# Sheet_1_2022-01-26.net
KiCad netlist of a schematic drawn in Altium Designer
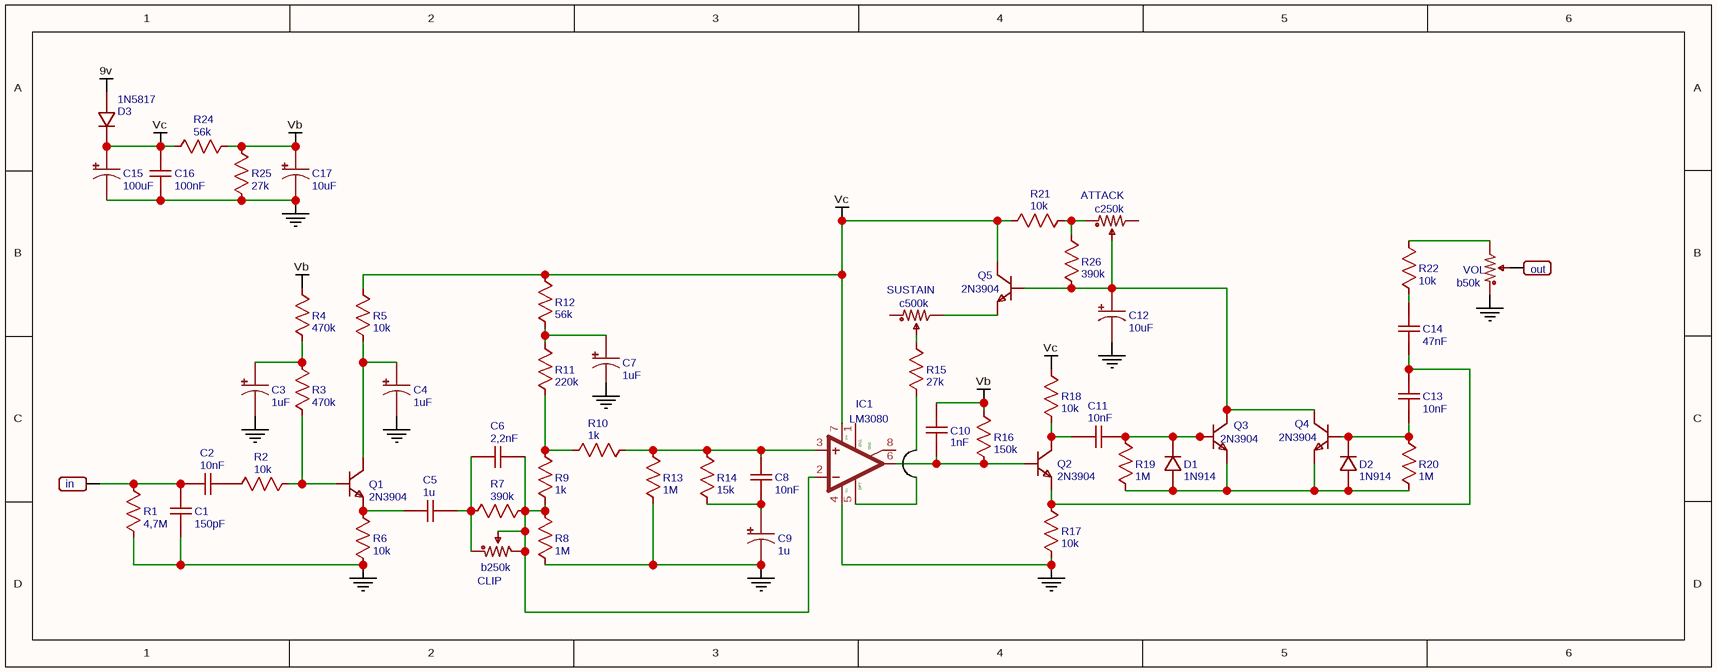
[diagram p0: Sheet_1_2022-01-26.schdoc]

(export (version "E")
  (design (tool "Eeschema 10.0.6"))
  (components
    (comp (ref "ATTACK")
      (value "c250k")
      (fields
        (field (name "BOM_SUPPLIER PART") "C125022")
        (field (name "BOM_MANUFACTURER PART") "3386P-1-101LF")
        (field (name "CONTRIBUTOR") "EasyEDA")
      )
      (libsource (lib "altium-import") (part "root_0_c250k_"))
    )
    (comp (ref "C1")
      (value "150pF")
      (fields (field (name "BOM_MANUFACTURER PART") "?"))
      (libsource (lib "altium-import") (part "root_0_150pF_"))
    )
    (comp (ref "C2")
      (value "10nF")
      (fields (field (name "BOM_MANUFACTURER PART") "?"))
      (libsource (lib "altium-import") (part "root_1_10nF_"))
    )
    (comp (ref "C3")
      (value "1uF")
      (fields (field (name "BOM_MANUFACTURER PART") "?"))
      (libsource (lib "altium-import") (part "root_0_1uF_"))
    )
    (comp (ref "C4")
      (value "1uF")
      (fields (field (name "BOM_MANUFACTURER PART") "?"))
      (libsource (lib "altium-import") (part "root_0_1uF_"))
    )
    (comp (ref "C5")
      (value "1u")
      (fields (field (name "BOM_MANUFACTURER PART") "?"))
      (libsource (lib "altium-import") (part "root_1_1u_"))
    )
    (comp (ref "C6")
      (value "2,2nF")
      (fields (field (name "BOM_MANUFACTURER PART") "?"))
      (libsource (lib "altium-import") (part "root_1_2,2nF_"))
    )
    (comp (ref "C7")
      (value "1uF")
      (fields (field (name "BOM_MANUFACTURER PART") "?"))
      (libsource (lib "altium-import") (part "root_0_1uF_"))
    )
    (comp (ref "C8")
      (value "10nF")
      (fields (field (name "BOM_MANUFACTURER PART") "?"))
      (libsource (lib "altium-import") (part "root_0_10nF_"))
    )
    (comp (ref "C9")
      (value "1u")
      (fields (field (name "BOM_MANUFACTURER PART") "?"))
      (libsource (lib "altium-import") (part "root_0_1u_"))
    )
    (comp (ref "C10")
      (value "1nF")
      (fields (field (name "BOM_MANUFACTURER PART") "?"))
      (libsource (lib "altium-import") (part "root_0_1nF_"))
    )
    (comp (ref "C11")
      (value "10nF")
      (fields (field (name "BOM_MANUFACTURER PART") "?"))
      (libsource (lib "altium-import") (part "root_1_10nF_"))
    )
    (comp (ref "C12")
      (value "10uF")
      (fields (field (name "BOM_MANUFACTURER PART") "?"))
      (libsource (lib "altium-import") (part "root_0_10uF_"))
    )
    (comp (ref "C13")
      (value "10nF")
      (fields (field (name "BOM_MANUFACTURER PART") "?"))
      (libsource (lib "altium-import") (part "root_0_10nF_"))
    )
    (comp (ref "C14")
      (value "47nF")
      (fields (field (name "BOM_MANUFACTURER PART") "?"))
      (libsource (lib "altium-import") (part "root_0_47nF_"))
    )
    (comp (ref "C15")
      (value "100uF")
      (fields (field (name "BOM_MANUFACTURER PART") "?"))
      (libsource (lib "altium-import") (part "root_0_100uF_"))
    )
    (comp (ref "C16")
      (value "100nF")
      (fields (field (name "BOM_MANUFACTURER PART") "?"))
      (libsource (lib "altium-import") (part "root_0_100nF_"))
    )
    (comp (ref "C17")
      (value "10uF")
      (fields (field (name "BOM_MANUFACTURER PART") "?"))
      (libsource (lib "altium-import") (part "root_0_10uF_"))
    )
    (comp (ref "CLIP")
      (value "b250k")
      (fields
        (field (name "BOM_SUPPLIER PART") "C125022")
        (field (name "BOM_MANUFACTURER PART") "3386P-1-101LF")
        (field (name "CONTRIBUTOR") "EasyEDA")
      )
      (libsource (lib "altium-import") (part "root_0_b250k_"))
    )
    (comp (ref "D1")
      (value "1N914")
      (fields (field (name "BOM_SUPPLIER PART") "C54037") (field (name "BOM_MANUFACTURER PART") "1N4448"))
      (libsource (lib "altium-import") (part "root_1_1N914_"))
    )
    (comp (ref "D2")
      (value "1N914")
      (fields (field (name "BOM_SUPPLIER PART") "C54037") (field (name "BOM_MANUFACTURER PART") "1N4448"))
      (libsource (lib "altium-import") (part "root_1_1N914_"))
    )
    (comp (ref "D3")
      (value "1N5817")
      (fields (field (name "BOM_SUPPLIER PART") "C54037") (field (name "BOM_MANUFACTURER PART") "1N4448"))
      (libsource (lib "altium-import") (part "root_1_1N5817_"))
    )
    (comp (ref "IC1")
      (value "LM3080")
      (description "OP AMP")
      (fields (field (name "BOM_MANUFACTURER PART") "?"))
      (libsource (lib "altium-import") (part "root_0_LM3080_"))
    )
    (comp (ref "P1")
      (value "in")
      (fields
        (field (name "BOM_SUPPLIER PART") "C81276")
        (field (name "BOM_MANUFACTURER PART") "Header-Male-2.54_1x1")
      )
      (libsource (lib "altium-import") (part "root_0_in_"))
    )
    (comp (ref "P2")
      (value "out")
      (fields
        (field (name "BOM_SUPPLIER PART") "C81276")
        (field (name "BOM_MANUFACTURER PART") "Header-Male-2.54_1x1")
      )
      (libsource (lib "altium-import") (part "root_0_out_"))
    )
    (comp (ref "Q1")
      (value "2N3904")
      (fields (field (name "BOM_SUPPLIER PART") "C118538"))
      (libsource (lib "") (part "root_0_2N3904__1"))
    )
    (comp (ref "Q2")
      (value "2N3904")
      (fields (field (name "BOM_SUPPLIER PART") "C118538"))
      (libsource (lib "") (part "root_0_2N3904__1"))
    )
    (comp (ref "Q3")
      (value "2N3904")
      (fields (field (name "BOM_SUPPLIER PART") "C118538"))
      (libsource (lib "") (part "root_0_2N3904__1"))
    )
    (comp (ref "Q4")
      (value "2N3904")
      (fields (field (name "BOM_SUPPLIER PART") "C118538"))
      (libsource (lib "altium-import") (part "root_0_2N3904_"))
    )
    (comp (ref "Q5")
      (value "2N3904")
      (fields (field (name "BOM_SUPPLIER PART") "C118538"))
      (libsource (lib "altium-import") (part "root_0_2N3904_"))
    )
    (comp (ref "R1")
      (value "4,7M")
      (fields (field (name "BOM_MANUFACTURER PART") "?"))
      (libsource (lib "altium-import") (part "root_1_4,7M_"))
    )
    (comp (ref "R2")
      (value "10k")
      (fields (field (name "BOM_MANUFACTURER PART") "?"))
      (libsource (lib "altium-import") (part "root_0_10k_"))
    )
    (comp (ref "R3")
      (value "470k")
      (fields (field (name "BOM_MANUFACTURER PART") "?"))
      (libsource (lib "altium-import") (part "root_1_470k_"))
    )
    (comp (ref "R4")
      (value "470k")
      (fields (field (name "BOM_MANUFACTURER PART") "?"))
      (libsource (lib "altium-import") (part "root_1_470k_"))
    )
    (comp (ref "R5")
      (value "10k")
      (fields (field (name "BOM_MANUFACTURER PART") "?"))
      (libsource (lib "altium-import") (part "root_1_10k_"))
    )
    (comp (ref "R6")
      (value "10k")
      (fields (field (name "BOM_MANUFACTURER PART") "?"))
      (libsource (lib "altium-import") (part "root_1_10k_"))
    )
    (comp (ref "R7")
      (value "390k")
      (fields (field (name "BOM_MANUFACTURER PART") "?"))
      (libsource (lib "altium-import") (part "root_0_390k_"))
    )
    (comp (ref "R8")
      (value "1M")
      (fields (field (name "BOM_MANUFACTURER PART") "?"))
      (libsource (lib "altium-import") (part "root_1_1M_"))
    )
    (comp (ref "R9")
      (value "1k")
      (fields (field (name "BOM_MANUFACTURER PART") "?"))
      (libsource (lib "altium-import") (part "root_1_1k_"))
    )
    (comp (ref "R10")
      (value "1k")
      (fields (field (name "BOM_MANUFACTURER PART") "?"))
      (libsource (lib "altium-import") (part "root_2_1k_"))
    )
    (comp (ref "R11")
      (value "220k")
      (fields (field (name "BOM_MANUFACTURER PART") "?"))
      (libsource (lib "altium-import") (part "root_1_220k_"))
    )
    (comp (ref "R12")
      (value "56k")
      (fields (field (name "BOM_MANUFACTURER PART") "?"))
      (libsource (lib "altium-import") (part "root_1_56k_"))
    )
    (comp (ref "R13")
      (value "1M")
      (fields (field (name "BOM_MANUFACTURER PART") "?"))
      (libsource (lib "altium-import") (part "root_1_1M_"))
    )
    (comp (ref "R14")
      (value "15k")
      (fields (field (name "BOM_MANUFACTURER PART") "?"))
      (libsource (lib "altium-import") (part "root_1_15k_"))
    )
    (comp (ref "R15")
      (value "27k")
      (fields (field (name "BOM_MANUFACTURER PART") "?"))
      (libsource (lib "altium-import") (part "root_1_27k_"))
    )
    (comp (ref "R16")
      (value "150k")
      (fields (field (name "BOM_MANUFACTURER PART") "?"))
      (libsource (lib "altium-import") (part "root_1_150k_"))
    )
    (comp (ref "R17")
      (value "10k")
      (fields (field (name "BOM_MANUFACTURER PART") "?"))
      (libsource (lib "altium-import") (part "root_1_10k_"))
    )
    (comp (ref "R18")
      (value "10k")
      (fields (field (name "BOM_MANUFACTURER PART") "?"))
      (libsource (lib "altium-import") (part "root_1_10k_"))
    )
    (comp (ref "R19")
      (value "1M")
      (fields (field (name "BOM_MANUFACTURER PART") "?"))
      (libsource (lib "altium-import") (part "root_1_1M_"))
    )
    (comp (ref "R20")
      (value "1M")
      (fields (field (name "BOM_MANUFACTURER PART") "?"))
      (libsource (lib "altium-import") (part "root_1_1M_"))
    )
    (comp (ref "R21")
      (value "10k")
      (fields (field (name "BOM_MANUFACTURER PART") "?"))
      (libsource (lib "altium-import") (part "root_0_10k_"))
    )
    (comp (ref "R22")
      (value "10k")
      (fields (field (name "BOM_MANUFACTURER PART") "?"))
      (libsource (lib "altium-import") (part "root_1_10k_"))
    )
    (comp (ref "R24")
      (value "56k")
      (fields (field (name "BOM_MANUFACTURER PART") "?"))
      (libsource (lib "altium-import") (part "root_0_56k_"))
    )
    (comp (ref "R25")
      (value "27k")
      (fields (field (name "BOM_MANUFACTURER PART") "?"))
      (libsource (lib "altium-import") (part "root_1_27k_"))
    )
    (comp (ref "R26")
      (value "390k")
      (fields (field (name "BOM_MANUFACTURER PART") "?"))
      (libsource (lib "altium-import") (part "root_1_390k_"))
    )
    (comp (ref "SUSTAIN")
      (value "c500k")
      (fields
        (field (name "BOM_SUPPLIER PART") "C125022")
        (field (name "BOM_MANUFACTURER PART") "3386P-1-101LF")
        (field (name "CONTRIBUTOR") "EasyEDA")
      )
      (libsource (lib "altium-import") (part "root_0_c500k_"))
    )
    (comp (ref "VOL")
      (value "b50k")
      (fields
        (field (name "BOM_SUPPLIER PART") "C125022")
        (field (name "BOM_MANUFACTURER PART") "3386P-1-101LF")
        (field (name "CONTRIBUTOR") "EasyEDA")
      )
      (libsource (lib "altium-import") (part "root_1_b50k_"))
    )
  )
  (nets
    (net (code "1") (name "9v") (class "Default")
      (node (ref "D3") (pin "1") (pinfunction "A_1") (pintype "passive"))
    )
    (net (code "2") (name "GND") (class "Default")
      (node (ref "C1") (pin "1") (pinfunction "1_1") (pintype "passive"))
      (node (ref "C12") (pin "2") (pinfunction "2_2") (pintype "passive"))
      (node (ref "C15") (pin "2") (pinfunction "2_2") (pintype "passive"))
      (node (ref "C16") (pin "1") (pinfunction "1_1") (pintype "passive"))
      (node (ref "C17") (pin "2") (pinfunction "2_2") (pintype "passive"))
      (node (ref "C3") (pin "2") (pinfunction "2_2") (pintype "passive"))
      (node (ref "C4") (pin "2") (pinfunction "2_2") (pintype "passive"))
      (node (ref "C9") (pin "2") (pinfunction "2_2") (pintype "passive"))
      (node (ref "IC1") (pin "4") (pinfunction "V-_4") (pintype "passive"))
      (node (ref "R1") (pin "1") (pinfunction "1_1") (pintype "passive"))
      (node (ref "R13") (pin "1") (pinfunction "1_1") (pintype "passive"))
      (node (ref "R17") (pin "1") (pinfunction "1_1") (pintype "passive"))
      (node (ref "R25") (pin "1") (pinfunction "1_1") (pintype "passive"))
      (node (ref "R6") (pin "1") (pinfunction "1_1") (pintype "passive"))
      (node (ref "R8") (pin "1") (pinfunction "1_1") (pintype "passive"))
      (node (ref "VOL") (pin "1") (pinfunction "1_1") (pintype "passive"))
    )
    (net (code "3") (name "Net-(ATTACK-Pad1)") (class "Default")
      (node (ref "ATTACK") (pin "1") (pinfunction "1_1") (pintype "passive"))
      (node (ref "R21") (pin "2") (pinfunction "2_2") (pintype "passive"))
      (node (ref "R26") (pin "2") (pinfunction "2_2") (pintype "passive"))
    )
    (net (code "4") (name "Net-(C1-Pad2)") (class "Default")
      (node (ref "C1") (pin "2") (pinfunction "2_2") (pintype "passive"))
      (node (ref "C2") (pin "2") (pinfunction "2_2") (pintype "passive"))
      (node (ref "P1") (pin "1") (pinfunction "1_1") (pintype "passive"))
      (node (ref "R1") (pin "2") (pinfunction "2_2") (pintype "passive"))
    )
    (net (code "5") (name "Net-(C2-Pad1)") (class "Default")
      (node (ref "C2") (pin "1") (pinfunction "1_1") (pintype "passive"))
      (node (ref "R2") (pin "1") (pinfunction "1_1") (pintype "passive"))
    )
    (net (code "6") (name "Net-(C3-Pad1)") (class "Default")
      (node (ref "C3") (pin "1") (pinfunction "1_1") (pintype "passive"))
      (node (ref "R3") (pin "2") (pinfunction "2_2") (pintype "passive"))
      (node (ref "R4") (pin "1") (pinfunction "1_1") (pintype "passive"))
    )
    (net (code "7") (name "Net-(C5-Pad1)") (class "Default")
      (node (ref "C5") (pin "1") (pinfunction "1_1") (pintype "passive"))
      (node (ref "C6") (pin "2") (pinfunction "2_2") (pintype "passive"))
      (node (ref "CLIP") (pin "1") (pinfunction "1_1") (pintype "passive"))
      (node (ref "R7") (pin "1") (pinfunction "1_1") (pintype "passive"))
    )
    (net (code "8") (name "Net-(C7-Pad1)") (class "Default")
      (node (ref "C7") (pin "1") (pinfunction "1_1") (pintype "passive"))
      (node (ref "R11") (pin "2") (pinfunction "2_2") (pintype "passive"))
      (node (ref "R12") (pin "1") (pinfunction "1_1") (pintype "passive"))
    )
    (net (code "9") (name "Net-(C8-Pad1)") (class "Default")
      (node (ref "C8") (pin "1") (pinfunction "1_1") (pintype "passive"))
      (node (ref "C9") (pin "1") (pinfunction "1_1") (pintype "passive"))
      (node (ref "R14") (pin "1") (pinfunction "1_1") (pintype "passive"))
    )
    (net (code "10") (name "Net-(C14-Pad2)") (class "Default")
      (node (ref "C14") (pin "2") (pinfunction "2_2") (pintype "passive"))
      (node (ref "R22") (pin "1") (pinfunction "1_1") (pintype "passive"))
    )
    (net (code "11") (name "Net-(D1-A)") (class "Default")
      (node (ref "D1") (pin "1") (pinfunction "A_1") (pintype "passive"))
      (node (ref "D2") (pin "1") (pinfunction "A_1") (pintype "passive"))
      (node (ref "Q3") (pin "1") (pinfunction "E_1") (pintype "passive"))
      (node (ref "Q4") (pin "1") (pinfunction "E_1") (pintype "passive"))
      (node (ref "R19") (pin "1") (pinfunction "1_1") (pintype "passive"))
      (node (ref "R20") (pin "1") (pinfunction "1_1") (pintype "passive"))
    )
    (net (code "12") (name "Net-(D1-K)") (class "Default")
      (node (ref "C11") (pin "1") (pinfunction "1_1") (pintype "passive"))
      (node (ref "D1") (pin "2") (pinfunction "K_2") (pintype "passive"))
      (node (ref "Q3") (pin "2") (pinfunction "B_2") (pintype "passive"))
      (node (ref "R19") (pin "2") (pinfunction "2_2") (pintype "passive"))
    )
    (net (code "13") (name "Net-(D2-K)") (class "Default")
      (node (ref "C13") (pin "1") (pinfunction "1_1") (pintype "passive"))
      (node (ref "D2") (pin "2") (pinfunction "K_2") (pintype "passive"))
      (node (ref "Q4") (pin "2") (pinfunction "B_2") (pintype "passive"))
      (node (ref "R20") (pin "2") (pinfunction "2_2") (pintype "passive"))
    )
    (net (code "14") (name "Net-(IC1-+IN)") (class "Default")
      (node (ref "C8") (pin "2") (pinfunction "2_2") (pintype "passive"))
      (node (ref "IC1") (pin "3") (pinfunction "+IN_3") (pintype "passive"))
      (node (ref "R10") (pin "1") (pinfunction "1_1") (pintype "passive"))
      (node (ref "R13") (pin "2") (pinfunction "2_2") (pintype "passive"))
      (node (ref "R14") (pin "2") (pinfunction "2_2") (pintype "passive"))
    )
    (net (code "15") (name "Net-(IC1--IN)") (class "Default")
      (node (ref "C6") (pin "1") (pinfunction "1_1") (pintype "passive"))
      (node (ref "CLIP") (pin "2") (pinfunction "2_2") (pintype "passive"))
      (node (ref "CLIP") (pin "3") (pinfunction "3_3") (pintype "passive"))
      (node (ref "IC1") (pin "2") (pinfunction "-IN_2") (pintype "passive"))
      (node (ref "R7") (pin "2") (pinfunction "2_2") (pintype "passive"))
      (node (ref "R8") (pin "2") (pinfunction "2_2") (pintype "passive"))
      (node (ref "R9") (pin "1") (pinfunction "1_1") (pintype "passive"))
    )
    (net (code "16") (name "Net-(IC1-OUT)") (class "Default")
      (node (ref "C10") (pin "1") (pinfunction "1_1") (pintype "passive"))
      (node (ref "IC1") (pin "6") (pinfunction "OUT_6") (pintype "passive"))
      (node (ref "Q2") (pin "2") (pinfunction "B_2") (pintype "passive"))
      (node (ref "R16") (pin "1") (pinfunction "1_1") (pintype "passive"))
    )
    (net (code "17") (name "Net-(P2-Pad1)") (class "Default")
      (node (ref "P2") (pin "1") (pinfunction "1_1") (pintype "passive"))
      (node (ref "VOL") (pin "2") (pinfunction "2_2") (pintype "passive"))
    )
    (net (code "18") (name "Net-(Q1-B)") (class "Default")
      (node (ref "Q1") (pin "2") (pinfunction "B_2") (pintype "passive"))
      (node (ref "R2") (pin "2") (pinfunction "2_2") (pintype "passive"))
      (node (ref "R3") (pin "1") (pinfunction "1_1") (pintype "passive"))
    )
    (net (code "19") (name "Net-(Q1-C)") (class "Default")
      (node (ref "C4") (pin "1") (pinfunction "1_1") (pintype "passive"))
      (node (ref "Q1") (pin "3") (pinfunction "C_3") (pintype "passive"))
      (node (ref "R5") (pin "1") (pinfunction "1_1") (pintype "passive"))
    )
    (net (code "20") (name "Net-(Q1-E)") (class "Default")
      (node (ref "C5") (pin "2") (pinfunction "2_2") (pintype "passive"))
      (node (ref "Q1") (pin "1") (pinfunction "E_1") (pintype "passive"))
      (node (ref "R6") (pin "2") (pinfunction "2_2") (pintype "passive"))
    )
    (net (code "21") (name "Net-(Q2-C)") (class "Default")
      (node (ref "C11") (pin "2") (pinfunction "2_2") (pintype "passive"))
      (node (ref "Q2") (pin "3") (pinfunction "C_3") (pintype "passive"))
      (node (ref "R18") (pin "1") (pinfunction "1_1") (pintype "passive"))
    )
    (net (code "22") (name "Net-(Q2-E)") (class "Default")
      (node (ref "C13") (pin "2") (pinfunction "2_2") (pintype "passive"))
      (node (ref "C14") (pin "1") (pinfunction "1_1") (pintype "passive"))
      (node (ref "Q2") (pin "1") (pinfunction "E_1") (pintype "passive"))
      (node (ref "R17") (pin "2") (pinfunction "2_2") (pintype "passive"))
    )
    (net (code "23") (name "Net-(Q3-C)") (class "Default")
      (node (ref "ATTACK") (pin "2") (pinfunction "2_2") (pintype "passive"))
      (node (ref "C12") (pin "1") (pinfunction "1_1") (pintype "passive"))
      (node (ref "Q3") (pin "3") (pinfunction "C_3") (pintype "passive"))
      (node (ref "Q4") (pin "3") (pinfunction "C_3") (pintype "passive"))
      (node (ref "Q5") (pin "2") (pinfunction "B_2") (pintype "passive"))
      (node (ref "R26") (pin "1") (pinfunction "1_1") (pintype "passive"))
    )
    (net (code "24") (name "Net-(Q5-E)") (class "Default")
      (node (ref "Q5") (pin "1") (pinfunction "E_1") (pintype "passive"))
      (node (ref "SUSTAIN") (pin "3") (pinfunction "3_3") (pintype "passive"))
    )
    (net (code "25") (name "Net-(R10-Pad2)") (class "Default")
      (node (ref "R10") (pin "2") (pinfunction "2_2") (pintype "passive"))
      (node (ref "R11") (pin "1") (pinfunction "1_1") (pintype "passive"))
      (node (ref "R9") (pin "2") (pinfunction "2_2") (pintype "passive"))
    )
    (net (code "26") (name "Net-(R15-Pad2)") (class "Default")
      (node (ref "R15") (pin "2") (pinfunction "2_2") (pintype "passive"))
      (node (ref "SUSTAIN") (pin "2") (pinfunction "2_2") (pintype "passive"))
    )
    (net (code "27") (name "Net-(R22-Pad2)") (class "Default")
      (node (ref "R22") (pin "2") (pinfunction "2_2") (pintype "passive"))
      (node (ref "VOL") (pin "3") (pinfunction "3_3") (pintype "passive"))
    )
    (net (code "28") (name "Vb") (class "Default")
      (node (ref "C10") (pin "2") (pinfunction "2_2") (pintype "passive"))
      (node (ref "C17") (pin "1") (pinfunction "1_1") (pintype "passive"))
      (node (ref "R16") (pin "2") (pinfunction "2_2") (pintype "passive"))
      (node (ref "R24") (pin "2") (pinfunction "2_2") (pintype "passive"))
      (node (ref "R25") (pin "2") (pinfunction "2_2") (pintype "passive"))
      (node (ref "R4") (pin "2") (pinfunction "2_2") (pintype "passive"))
    )
    (net (code "29") (name "Vc") (class "Default")
      (node (ref "C15") (pin "1") (pinfunction "1_1") (pintype "passive"))
      (node (ref "C16") (pin "2") (pinfunction "2_2") (pintype "passive"))
      (node (ref "D3") (pin "2") (pinfunction "K_2") (pintype "passive"))
      (node (ref "IC1") (pin "7") (pinfunction "V+_7") (pintype "passive"))
      (node (ref "Q5") (pin "3") (pinfunction "C_3") (pintype "passive"))
      (node (ref "R12") (pin "2") (pinfunction "2_2") (pintype "passive"))
      (node (ref "R18") (pin "2") (pinfunction "2_2") (pintype "passive"))
      (node (ref "R21") (pin "1") (pinfunction "1_1") (pintype "passive"))
      (node (ref "R24") (pin "1") (pinfunction "1_1") (pintype "passive"))
      (node (ref "R5") (pin "2") (pinfunction "2_2") (pintype "passive"))
    )
    (net (code "30") (name "unconnected-(ATTACK-Pad3)") (class "Default")
      (node (ref "ATTACK") (pin "3") (pinfunction "3_3") (pintype "passive"))
    )
    (net (code "31") (name "unconnected-(C7-Pad2)") (class "Default")
      (node (ref "C7") (pin "2") (pinfunction "2_2") (pintype "passive"))
    )
    (net (code "32") (name "unconnected-(IC1-ON1-Pad1)") (class "Default")
      (node (ref "IC1") (pin "1") (pinfunction "ON1_1") (pintype "passive"))
    )
    (net (code "33") (name "unconnected-(IC1-ON2-Pad8)") (class "Default")
      (node (ref "IC1") (pin "8") (pinfunction "ON2_8") (pintype "passive"))
    )
    (net (code "34") (name "unconnected-(IC1-OPT-Pad5)") (class "Default")
      (node (ref "IC1") (pin "5") (pinfunction "OPT_5") (pintype "passive"))
    )
    (net (code "35") (name "unconnected-(R15-Pad1)") (class "Default")
      (node (ref "R15") (pin "1") (pinfunction "1_1") (pintype "passive"))
    )
    (net (code "36") (name "unconnected-(SUSTAIN-Pad1)") (class "Default")
      (node (ref "SUSTAIN") (pin "1") (pinfunction "1_1") (pintype "passive"))
    )
  )
)
